# i2c-splitter.net
KiCad netlist of a schematic drawn in EAGLE
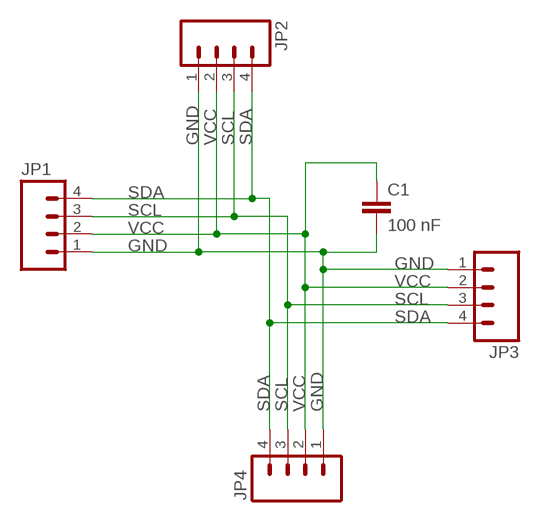
[diagram p0: schematic, sheet 1]

(export (version "E")
  (design (tool "Eeschema 10.0.6"))
  (components
    (comp (ref "C1")
      (value "100 nF")
      (footprint "eagle-import:C0805")
      (libsource (lib "eagle-import") (part "C-EUC0805"))
    )
    (comp (ref "JP1")
      (value "M04PTH")
      (footprint "eagle-import:1X04")
      (libsource (lib "eagle-import") (part "M04PTH"))
    )
    (comp (ref "JP2")
      (value "M04PTH")
      (footprint "eagle-import:1X04")
      (libsource (lib "eagle-import") (part "M04PTH"))
    )
    (comp (ref "JP3")
      (value "M04PTH")
      (footprint "eagle-import:1X04")
      (libsource (lib "eagle-import") (part "M04PTH"))
    )
    (comp (ref "JP4")
      (value "M04PTH")
      (footprint "eagle-import:1X04")
      (libsource (lib "eagle-import") (part "M04PTH"))
    )
  )
  (nets
    (net (code "1") (name "/GND") (class "Default")
      (node (ref "C1") (pin "2") (pinfunction "2_2") (pintype "passive"))
      (node (ref "JP1") (pin "1") (pinfunction "1_1") (pintype "passive"))
      (node (ref "JP2") (pin "1") (pinfunction "1_1") (pintype "passive"))
      (node (ref "JP3") (pin "1") (pinfunction "1_1") (pintype "passive"))
      (node (ref "JP4") (pin "1") (pinfunction "1_1") (pintype "passive"))
    )
    (net (code "2") (name "/SCL") (class "Default")
      (node (ref "JP1") (pin "3") (pinfunction "3_3") (pintype "passive"))
      (node (ref "JP2") (pin "3") (pinfunction "3_3") (pintype "passive"))
      (node (ref "JP3") (pin "3") (pinfunction "3_3") (pintype "passive"))
      (node (ref "JP4") (pin "3") (pinfunction "3_3") (pintype "passive"))
    )
    (net (code "3") (name "/SDA") (class "Default")
      (node (ref "JP1") (pin "4") (pinfunction "4_4") (pintype "passive"))
      (node (ref "JP2") (pin "4") (pinfunction "4_4") (pintype "passive"))
      (node (ref "JP3") (pin "4") (pinfunction "4_4") (pintype "passive"))
      (node (ref "JP4") (pin "4") (pinfunction "4_4") (pintype "passive"))
    )
    (net (code "4") (name "/VCC") (class "Default")
      (node (ref "C1") (pin "1") (pinfunction "1_1") (pintype "passive"))
      (node (ref "JP1") (pin "2") (pinfunction "2_2") (pintype "passive"))
      (node (ref "JP2") (pin "2") (pinfunction "2_2") (pintype "passive"))
      (node (ref "JP3") (pin "2") (pinfunction "2_2") (pintype "passive"))
      (node (ref "JP4") (pin "2") (pinfunction "2_2") (pintype "passive"))
    )
  )
)
